# SCH_Ghost_2024-10-19.net
KiCad netlist of a schematic drawn in EasyEDA
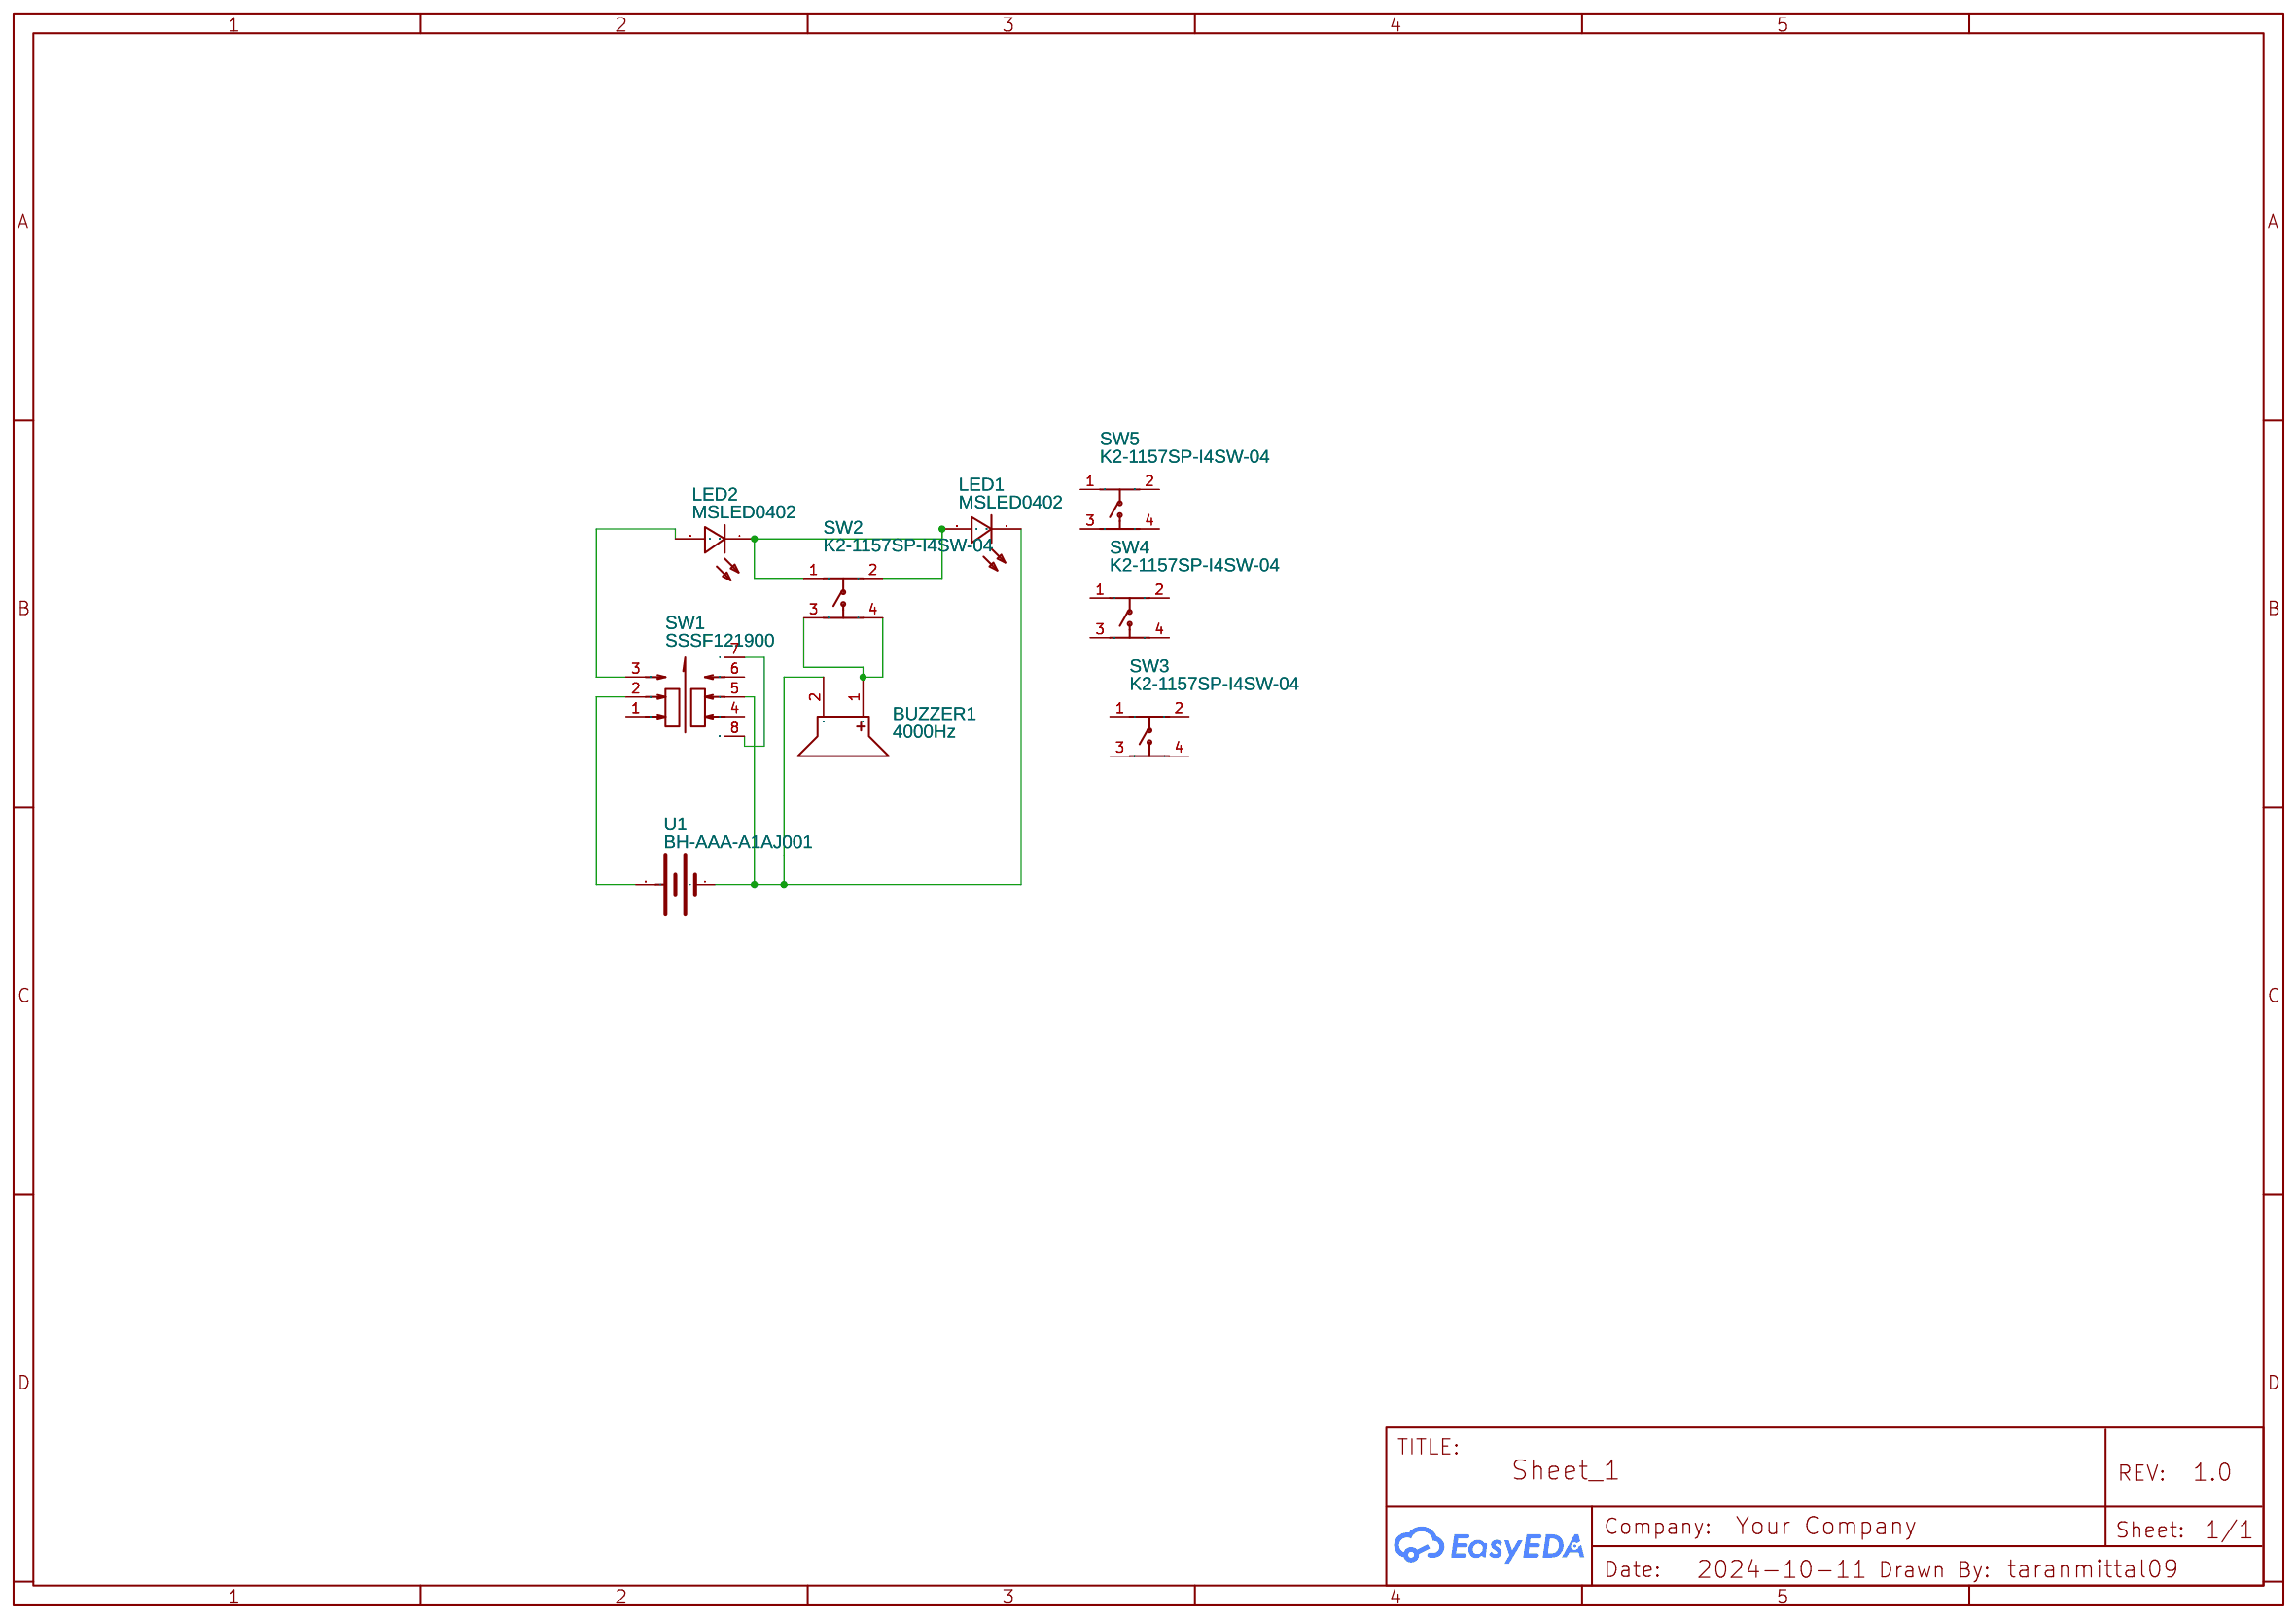
[diagram p0: schematic sheet]

(export (version "E")
  (design (tool "Eeschema 10.0.6"))
  (components
    (comp (ref "BUZZER1")
      (value "4000Hz")
      (fields (field (name "Manufacturer Part") "HNR-1407A") (field (name "Manufacturer") "华能"))
      (libsource (lib "") (part "HNR-1407A"))
    )
    (comp (ref "LED1") (value "MSLED0402") (libsource (lib "") (part "MSLED0402")))
    (comp (ref "LED2") (value "MSLED0402") (libsource (lib "") (part "MSLED0402")))
    (comp (ref "SW1")
      (value "SSSF121900")
      (fields (field (name "Manufacturer") "ALPSALPINE(阿尔卑斯阿尔派)"))
      (libsource (lib "") (part "SSSF121900"))
    )
    (comp (ref "SW2")
      (value "K2-1157SP-I4SW-04")
      (fields (field (name "Manufacturer Part") "K2-1157SP-I4SW-01") (field (name "Manufacturer") "韩国韩荣"))
      (libsource (lib "") (part "K2-1157SP-I4SW-04"))
    )
    (comp (ref "SW3")
      (value "K2-1157SP-I4SW-04")
      (fields (field (name "Manufacturer Part") "K2-1157SP-I4SW-01") (field (name "Manufacturer") "韩国韩荣"))
      (libsource (lib "") (part "K2-1157SP-I4SW-04"))
    )
    (comp (ref "SW4")
      (value "K2-1157SP-I4SW-04")
      (fields (field (name "Manufacturer Part") "K2-1157SP-I4SW-01") (field (name "Manufacturer") "韩国韩荣"))
      (libsource (lib "") (part "K2-1157SP-I4SW-04"))
    )
    (comp (ref "SW5")
      (value "K2-1157SP-I4SW-04")
      (fields (field (name "Manufacturer Part") "K2-1157SP-I4SW-01") (field (name "Manufacturer") "韩国韩荣"))
      (libsource (lib "") (part "K2-1157SP-I4SW-04"))
    )
    (comp (ref "U1")
      (value "BH-AAA-A1AJ001")
      (fields (field (name "Manufacturer") "MYOUNG(美阳)"))
      (libsource (lib "") (part "BH-AAA-A1AJ001"))
    )
  )
  (nets
    (net (code "1") (name "Net-(BUZZER1-Pad1)") (class "Default")
      (node (ref "BUZZER1") (pin "1") (pinfunction "1_1") (pintype "unspecified"))
      (node (ref "SW2") (pin "3") (pinfunction "3_3") (pintype "unspecified"))
      (node (ref "SW2") (pin "4") (pinfunction "4_4") (pintype "unspecified"))
    )
    (net (code "2") (name "Net-(LED1-A)") (class "Default")
      (node (ref "LED1") (pin "2") (pinfunction "A_2") (pintype "unspecified"))
      (node (ref "LED2") (pin "1") (pinfunction "C_1") (pintype "unspecified"))
      (node (ref "SW2") (pin "1") (pinfunction "1_1") (pintype "unspecified"))
      (node (ref "SW2") (pin "2") (pinfunction "2_2") (pintype "unspecified"))
    )
    (net (code "3") (name "Net-(LED1-C)") (class "Default")
      (node (ref "BUZZER1") (pin "2") (pinfunction "2_2") (pintype "unspecified"))
      (node (ref "LED1") (pin "1") (pinfunction "C_1") (pintype "unspecified"))
      (node (ref "SW1") (pin "5") (pinfunction "5_5") (pintype "unspecified"))
      (node (ref "U1") (pin "1") (pinfunction "-_1") (pintype "passive"))
    )
    (net (code "4") (name "Net-(LED2-A)") (class "Default")
      (node (ref "LED2") (pin "2") (pinfunction "A_2") (pintype "unspecified"))
      (node (ref "SW1") (pin "3") (pinfunction "3_3") (pintype "unspecified"))
    )
    (net (code "5") (name "Net-(SW1-Pad7)") (class "Default")
      (node (ref "SW1") (pin "7") (pinfunction "7_7") (pintype "unspecified"))
      (node (ref "SW1") (pin "8") (pinfunction "8_8") (pintype "unspecified"))
    )
    (net (code "6") (name "Net-(U1-+)") (class "Default")
      (node (ref "SW1") (pin "2") (pinfunction "2_2") (pintype "unspecified"))
      (node (ref "U1") (pin "2") (pinfunction "+_2") (pintype "passive"))
    )
    (net (code "7") (name "unconnected-(SW1-Pad1)") (class "Default")
      (node (ref "SW1") (pin "1") (pinfunction "1_1") (pintype "unspecified"))
    )
    (net (code "8") (name "unconnected-(SW1-Pad4)") (class "Default")
      (node (ref "SW1") (pin "4") (pinfunction "4_4") (pintype "unspecified"))
    )
    (net (code "9") (name "unconnected-(SW1-Pad6)") (class "Default")
      (node (ref "SW1") (pin "6") (pinfunction "6_6") (pintype "unspecified"))
    )
    (net (code "10") (name "unconnected-(SW3-Pad1)") (class "Default")
      (node (ref "SW3") (pin "1") (pinfunction "1_1") (pintype "unspecified"))
    )
    (net (code "11") (name "unconnected-(SW3-Pad2)") (class "Default")
      (node (ref "SW3") (pin "2") (pinfunction "2_2") (pintype "unspecified"))
    )
    (net (code "12") (name "unconnected-(SW3-Pad3)") (class "Default")
      (node (ref "SW3") (pin "3") (pinfunction "3_3") (pintype "unspecified"))
    )
    (net (code "13") (name "unconnected-(SW3-Pad4)") (class "Default")
      (node (ref "SW3") (pin "4") (pinfunction "4_4") (pintype "unspecified"))
    )
    (net (code "14") (name "unconnected-(SW4-Pad1)") (class "Default")
      (node (ref "SW4") (pin "1") (pinfunction "1_1") (pintype "unspecified"))
    )
    (net (code "15") (name "unconnected-(SW4-Pad2)") (class "Default")
      (node (ref "SW4") (pin "2") (pinfunction "2_2") (pintype "unspecified"))
    )
    (net (code "16") (name "unconnected-(SW4-Pad3)") (class "Default")
      (node (ref "SW4") (pin "3") (pinfunction "3_3") (pintype "unspecified"))
    )
    (net (code "17") (name "unconnected-(SW4-Pad4)") (class "Default")
      (node (ref "SW4") (pin "4") (pinfunction "4_4") (pintype "unspecified"))
    )
    (net (code "18") (name "unconnected-(SW5-Pad1)") (class "Default")
      (node (ref "SW5") (pin "1") (pinfunction "1_1") (pintype "unspecified"))
    )
    (net (code "19") (name "unconnected-(SW5-Pad2)") (class "Default")
      (node (ref "SW5") (pin "2") (pinfunction "2_2") (pintype "unspecified"))
    )
    (net (code "20") (name "unconnected-(SW5-Pad3)") (class "Default")
      (node (ref "SW5") (pin "3") (pinfunction "3_3") (pintype "unspecified"))
    )
    (net (code "21") (name "unconnected-(SW5-Pad4)") (class "Default")
      (node (ref "SW5") (pin "4") (pinfunction "4_4") (pintype "unspecified"))
    )
  )
)
